# supervisor.net
KiCad netlist of a schematic drawn in EAGLE
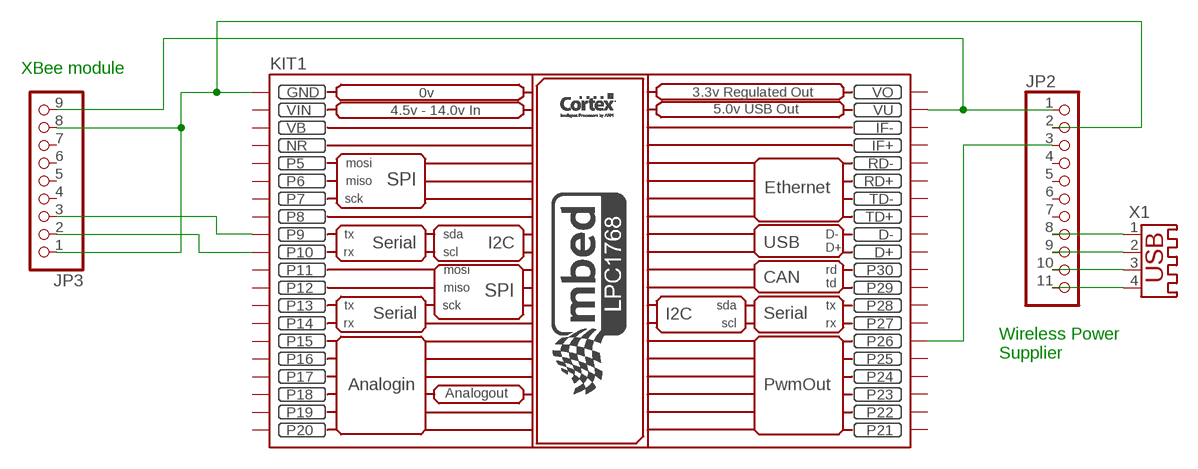
[diagram p0: schematic, sheet 1]

(export (version "E")
  (design (tool "Eeschema 10.0.6"))
  (components
    (comp (ref "JP2")
      (value "PINHD-1X11")
      (footprint "eagle-import:1X11")
      (libsource (lib "eagle-import") (part "PINHD-1X11"))
    )
    (comp (ref "JP3")
      (value "PINHD-1X9")
      (footprint "eagle-import:1X09")
      (libsource (lib "eagle-import") (part "PINHD-1X9"))
    )
    (comp (ref "KIT1")
      (value "MBED_NXP_LPC1768")
      (footprint "eagle-import:MBED-KIT")
      (libsource (lib "eagle-import") (part "MBED_NXP_LPC1768"))
    )
    (comp (ref "X1")
      (value "USB-A003")
      (footprint "eagle-import:USB-A003")
      (libsource (lib "eagle-import") (part "USB-A003"))
    )
  )
  (nets
    (net (code "1") (name "/NR") (class "Default")
      (node (ref "KIT1") (pin "NR") (pinfunction "NR_NR") (pintype "power_in"))
    )
    (net (code "2") (name "/VB") (class "Default")
      (node (ref "KIT1") (pin "VB") (pinfunction "VB_VB") (pintype "power_in"))
    )
    (net (code "3") (name "/VIN") (class "Default")
      (node (ref "KIT1") (pin "VIN") (pinfunction "VIN_VIN") (pintype "power_in"))
    )
    (net (code "4") (name "/VO") (class "Default")
      (node (ref "KIT1") (pin "VOUT") (pinfunction "VO_VOUT") (pintype "power_in"))
    )
    (net (code "5") (name "Net-(JP2-Pad1)") (class "Default")
      (node (ref "JP2") (pin "1") (pinfunction "1_1") (pintype "passive"))
      (node (ref "JP3") (pin "9") (pinfunction "9_9") (pintype "passive"))
      (node (ref "KIT1") (pin "VU") (pinfunction "VU_VU") (pintype "power_in"))
    )
    (net (code "6") (name "Net-(JP2-Pad2)") (class "Default")
      (node (ref "JP2") (pin "2") (pinfunction "2_2") (pintype "passive"))
      (node (ref "JP3") (pin "1") (pinfunction "1_1") (pintype "passive"))
      (node (ref "JP3") (pin "8") (pinfunction "8_8") (pintype "passive"))
      (node (ref "KIT1") (pin "GND") (pinfunction "GND_GND") (pintype "power_in"))
    )
    (net (code "7") (name "Net-(JP2-Pad8)") (class "Default")
      (node (ref "JP2") (pin "8") (pinfunction "8_8") (pintype "passive"))
      (node (ref "X1") (pin "1") (pinfunction "1_1") (pintype "passive"))
    )
    (net (code "8") (name "Net-(JP2-Pad9)") (class "Default")
      (node (ref "JP2") (pin "9") (pinfunction "9_9") (pintype "passive"))
      (node (ref "X1") (pin "2") (pinfunction "2_2") (pintype "passive"))
    )
    (net (code "9") (name "Net-(JP2-Pad10)") (class "Default")
      (node (ref "JP2") (pin "10") (pinfunction "10_10") (pintype "passive"))
      (node (ref "X1") (pin "3") (pinfunction "3_3") (pintype "passive"))
    )
    (net (code "10") (name "Net-(JP2-Pad11)") (class "Default")
      (node (ref "JP2") (pin "11") (pinfunction "11_11") (pintype "passive"))
      (node (ref "X1") (pin "4") (pinfunction "4_4") (pintype "passive"))
    )
    (net (code "11") (name "Net-(KIT1-P9)") (class "Default")
      (node (ref "JP3") (pin "3") (pinfunction "3_3") (pintype "passive"))
      (node (ref "KIT1") (pin "P$9") (pinfunction "P9_P$9") (pintype "bidirectional"))
    )
    (net (code "12") (name "Net-(KIT1-P10)") (class "Default")
      (node (ref "JP3") (pin "2") (pinfunction "2_2") (pintype "passive"))
      (node (ref "KIT1") (pin "P$10") (pinfunction "P10_P$10") (pintype "bidirectional"))
    )
    (net (code "13") (name "Net-(KIT1-P26)") (class "Default")
      (node (ref "JP2") (pin "3") (pinfunction "3_3") (pintype "passive"))
      (node (ref "KIT1") (pin "P$26") (pinfunction "P26_P$26") (pintype "bidirectional"))
    )
    (net (code "14") (name "unconnected-(JP2-Pad4)") (class "Default")
      (node (ref "JP2") (pin "4") (pinfunction "4_4") (pintype "passive"))
    )
    (net (code "15") (name "unconnected-(JP2-Pad5)") (class "Default")
      (node (ref "JP2") (pin "5") (pinfunction "5_5") (pintype "passive"))
    )
    (net (code "16") (name "unconnected-(JP2-Pad6)") (class "Default")
      (node (ref "JP2") (pin "6") (pinfunction "6_6") (pintype "passive"))
    )
    (net (code "17") (name "unconnected-(JP2-Pad7)") (class "Default")
      (node (ref "JP2") (pin "7") (pinfunction "7_7") (pintype "passive"))
    )
    (net (code "18") (name "unconnected-(JP3-Pad4)") (class "Default")
      (node (ref "JP3") (pin "4") (pinfunction "4_4") (pintype "passive"))
    )
    (net (code "19") (name "unconnected-(JP3-Pad5)") (class "Default")
      (node (ref "JP3") (pin "5") (pinfunction "5_5") (pintype "passive"))
    )
    (net (code "20") (name "unconnected-(JP3-Pad6)") (class "Default")
      (node (ref "JP3") (pin "6") (pinfunction "6_6") (pintype "passive"))
    )
    (net (code "21") (name "unconnected-(JP3-Pad7)") (class "Default")
      (node (ref "JP3") (pin "7") (pinfunction "7_7") (pintype "passive"))
    )
    (net (code "22") (name "unconnected-(KIT1-P5-PadP$5)") (class "Default")
      (node (ref "KIT1") (pin "P$5") (pinfunction "P5_P$5") (pintype "bidirectional"))
    )
    (net (code "23") (name "unconnected-(KIT1-P6-PadP$6)") (class "Default")
      (node (ref "KIT1") (pin "P$6") (pinfunction "P6_P$6") (pintype "bidirectional"))
    )
    (net (code "24") (name "unconnected-(KIT1-P7-PadP$7)") (class "Default")
      (node (ref "KIT1") (pin "P$7") (pinfunction "P7_P$7") (pintype "bidirectional"))
    )
    (net (code "25") (name "unconnected-(KIT1-P8-PadP$8)") (class "Default")
      (node (ref "KIT1") (pin "P$8") (pinfunction "P8_P$8") (pintype "bidirectional"))
    )
    (net (code "26") (name "unconnected-(KIT1-P11-PadP$11)") (class "Default")
      (node (ref "KIT1") (pin "P$11") (pinfunction "P11_P$11") (pintype "bidirectional"))
    )
    (net (code "27") (name "unconnected-(KIT1-P12-PadP$12)") (class "Default")
      (node (ref "KIT1") (pin "P$12") (pinfunction "P12_P$12") (pintype "bidirectional"))
    )
    (net (code "28") (name "unconnected-(KIT1-P13-PadP$13)") (class "Default")
      (node (ref "KIT1") (pin "P$13") (pinfunction "P13_P$13") (pintype "bidirectional"))
    )
    (net (code "29") (name "unconnected-(KIT1-P14-PadP$14)") (class "Default")
      (node (ref "KIT1") (pin "P$14") (pinfunction "P14_P$14") (pintype "bidirectional"))
    )
    (net (code "30") (name "unconnected-(KIT1-P15-PadP$15)") (class "Default")
      (node (ref "KIT1") (pin "P$15") (pinfunction "P15_P$15") (pintype "bidirectional"))
    )
    (net (code "31") (name "unconnected-(KIT1-P16-PadP$16)") (class "Default")
      (node (ref "KIT1") (pin "P$16") (pinfunction "P16_P$16") (pintype "bidirectional"))
    )
    (net (code "32") (name "unconnected-(KIT1-P17-PadP$17)") (class "Default")
      (node (ref "KIT1") (pin "P$17") (pinfunction "P17_P$17") (pintype "bidirectional"))
    )
    (net (code "33") (name "unconnected-(KIT1-P18-PadP$18)") (class "Default")
      (node (ref "KIT1") (pin "P$18") (pinfunction "P18_P$18") (pintype "bidirectional"))
    )
    (net (code "34") (name "unconnected-(KIT1-P19-PadP$19)") (class "Default")
      (node (ref "KIT1") (pin "P$19") (pinfunction "P19_P$19") (pintype "bidirectional"))
    )
    (net (code "35") (name "unconnected-(KIT1-P20-PadP$20)") (class "Default")
      (node (ref "KIT1") (pin "P$20") (pinfunction "P20_P$20") (pintype "bidirectional"))
    )
    (net (code "36") (name "unconnected-(KIT1-P21-PadP$21)") (class "Default")
      (node (ref "KIT1") (pin "P$21") (pinfunction "P21_P$21") (pintype "bidirectional"))
    )
    (net (code "37") (name "unconnected-(KIT1-P22-PadP$22)") (class "Default")
      (node (ref "KIT1") (pin "P$22") (pinfunction "P22_P$22") (pintype "bidirectional"))
    )
    (net (code "38") (name "unconnected-(KIT1-P23-PadP$23)") (class "Default")
      (node (ref "KIT1") (pin "P$23") (pinfunction "P23_P$23") (pintype "bidirectional"))
    )
    (net (code "39") (name "unconnected-(KIT1-P24-PadP$24)") (class "Default")
      (node (ref "KIT1") (pin "P$24") (pinfunction "P24_P$24") (pintype "bidirectional"))
    )
    (net (code "40") (name "unconnected-(KIT1-P25-PadP$25)") (class "Default")
      (node (ref "KIT1") (pin "P$25") (pinfunction "P25_P$25") (pintype "bidirectional"))
    )
    (net (code "41") (name "unconnected-(KIT1-P27-PadP$27)") (class "Default")
      (node (ref "KIT1") (pin "P$27") (pinfunction "P27_P$27") (pintype "bidirectional"))
    )
    (net (code "42") (name "unconnected-(KIT1-P28-PadP$28)") (class "Default")
      (node (ref "KIT1") (pin "P$28") (pinfunction "P28_P$28") (pintype "bidirectional"))
    )
    (net (code "43") (name "unconnected-(KIT1-P29-PadP$29)") (class "Default")
      (node (ref "KIT1") (pin "P$29") (pinfunction "P29_P$29") (pintype "bidirectional"))
    )
    (net (code "44") (name "unconnected-(KIT1-P30-PadP$30)") (class "Default")
      (node (ref "KIT1") (pin "P$30") (pinfunction "P30_P$30") (pintype "bidirectional"))
    )
    (net (code "45") (name "unconnected-(KIT1-PadD+)") (class "Default")
      (node (ref "KIT1") (pin "D+") (pinfunction "D+_D+") (pintype "bidirectional"))
    )
    (net (code "46") (name "unconnected-(KIT1-PadD-)") (class "Default")
      (node (ref "KIT1") (pin "D-") (pinfunction "D-_D-") (pintype "bidirectional"))
    )
    (net (code "47") (name "unconnected-(KIT1-PadIF+)") (class "Default")
      (node (ref "KIT1") (pin "IF+") (pinfunction "IF+_IF+") (pintype "bidirectional"))
    )
    (net (code "48") (name "unconnected-(KIT1-PadIF-)") (class "Default")
      (node (ref "KIT1") (pin "IF-") (pinfunction "IF-_IF-") (pintype "bidirectional"))
    )
    (net (code "49") (name "unconnected-(KIT1-PadRD+)") (class "Default")
      (node (ref "KIT1") (pin "RD+") (pinfunction "RD+_RD+") (pintype "bidirectional"))
    )
    (net (code "50") (name "unconnected-(KIT1-PadRD-)") (class "Default")
      (node (ref "KIT1") (pin "RD-") (pinfunction "RD-_RD-") (pintype "bidirectional"))
    )
    (net (code "51") (name "unconnected-(KIT1-PadTD+)") (class "Default")
      (node (ref "KIT1") (pin "TD+") (pinfunction "TD+_TD+") (pintype "bidirectional"))
    )
    (net (code "52") (name "unconnected-(KIT1-PadTD-)") (class "Default")
      (node (ref "KIT1") (pin "TD-") (pinfunction "TD-_TD-") (pintype "bidirectional"))
    )
  )
)
